# LCD4_3.net
KiCad netlist of a schematic drawn in Altium Designer
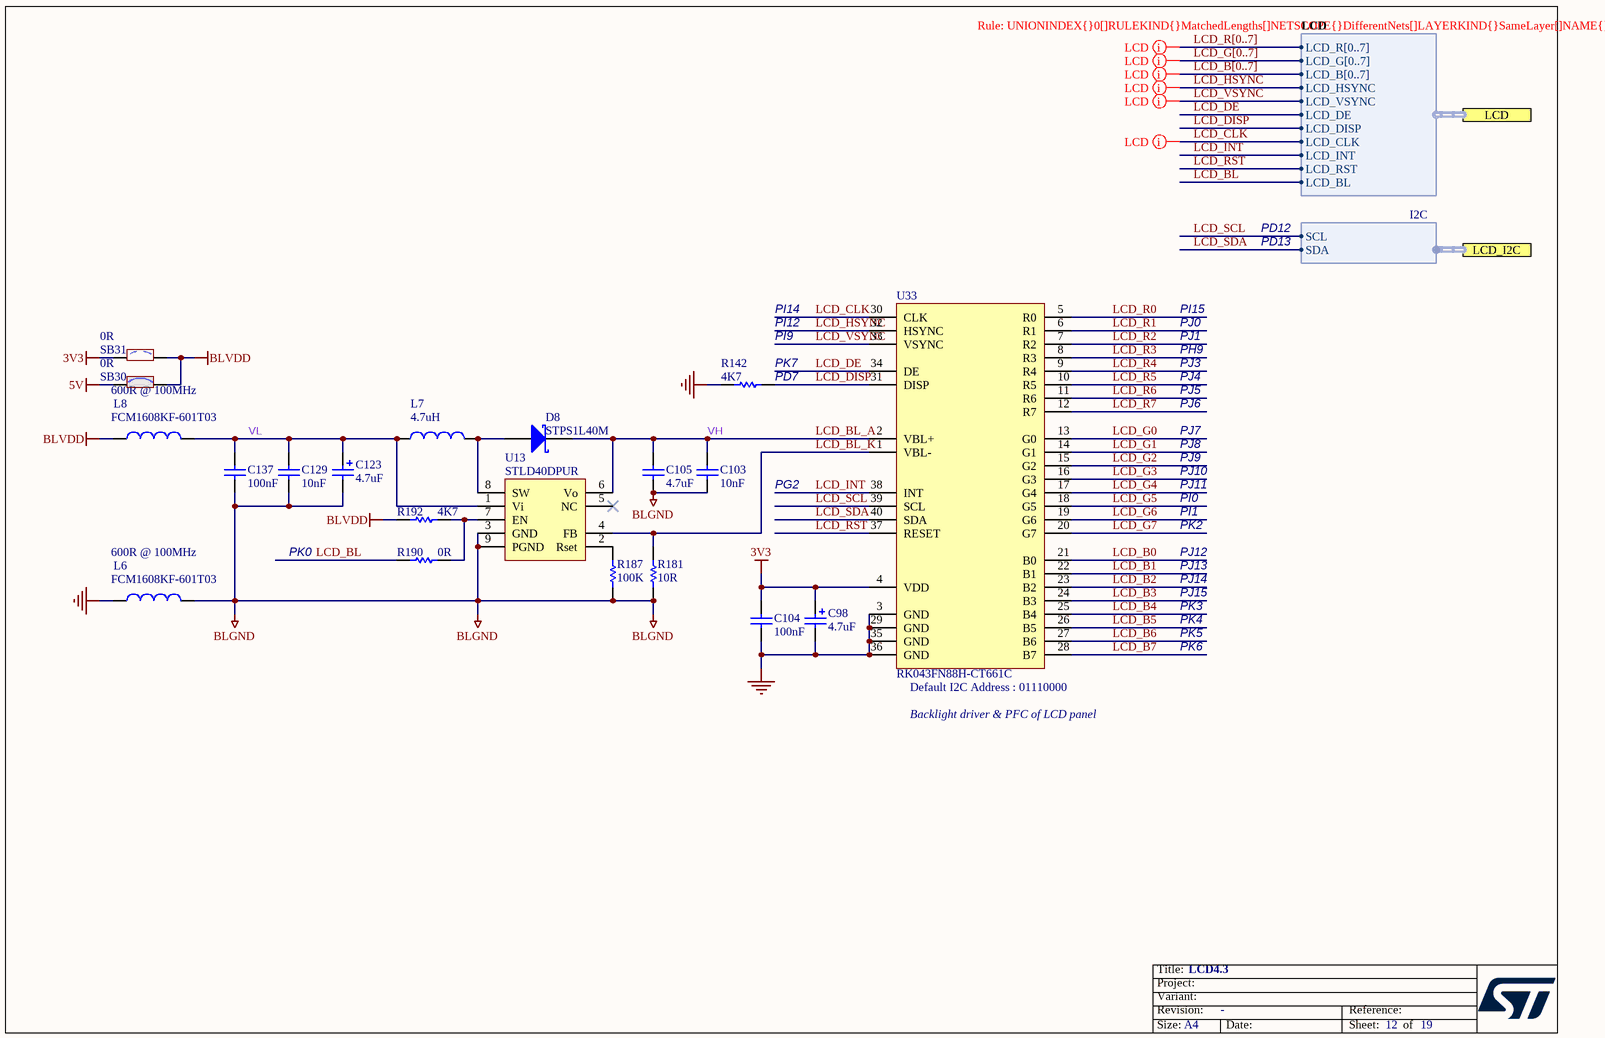
[diagram p0: LCD4.3.SchDoc]

(export (version "E")
  (design (tool "Eeschema 10.0.6"))
  (components
    (comp (ref "C98")
      (value "4.7uF")
      (footprint "CPOL_VISHAY_TANTAL-595D_1407_H220")
      (description "Capacitor, Tantalum, 4.7uF, 16V, +/-10%, 595D case A")
      (fields
        (field (name "INTERNAL_PART_NUMBER") "MCD-00595")
        (field (name "MANUFACTURER_PART_NUMBER") "595D475X9016A2T")
        (field (name "PROVIDED_BY") "Subcon")
      )
      (libsource (lib "MCD_PARTS_database") (part "Cap_POL_TANA"))
    )
    (comp (ref "C103")
      (value "10nF")
      (footprint "C0603")
      (description "Capacitor, MLCC, 10nF, 50V, X7R, +/-10%, 0603, T=0.8mm")
      (fields
        (field (name "INTERNAL_PART_NUMBER") "MCD-00017")
        (field (name "MANUFACTURER_PART_NUMBER") "CC0603KRX7R9BB103")
      )
      (libsource (lib "MCD_PARTS_database") (part "Capacitor"))
    )
    (comp (ref "C104")
      (value "100nF")
      (footprint "C0402")
      (description "Capacitor, MLCC, 100nF, 16V, X7R, +/-10%, 0402, T=0.5mm")
      (fields
        (field (name "INTERNAL_PART_NUMBER") "MCD-00006")
        (field (name "MANUFACTURER_PART_NUMBER") "CC0402KRX7R7BB104")
      )
      (libsource (lib "MCD_PARTS_database") (part "Capacitor"))
    )
    (comp (ref "C105")
      (value "4.7uF")
      (footprint "C1206_H1P25")
      (description "Capacitor, MLCC, 4.7uF, 50V, X7R, 10%, 1206, T=1,27mm")
      (fields
        (field (name "INTERNAL_PART_NUMBER") "MCD-00013")
        (field (name "MANUFACTURER_PART_NUMBER") "12065C475KAT2A")
        (field (name "PROVIDED_BY") "Subcon")
      )
      (libsource (lib "MCD_PARTS_database") (part "Capacitor"))
    )
    (comp (ref "C123")
      (value "4.7uF")
      (footprint "CPOL_VISHAY_TANTAL-595D_1407_H220")
      (description "Capacitor, Tantalum, 4.7uF, 16V, +/-10%, 595D case A")
      (fields
        (field (name "INTERNAL_PART_NUMBER") "MCD-00595")
        (field (name "MANUFACTURER_PART_NUMBER") "595D475X9016A2T")
        (field (name "PROVIDED_BY") "Subcon")
      )
      (libsource (lib "MCD_PARTS_database") (part "Cap_POL_TANA"))
    )
    (comp (ref "C129")
      (value "10nF")
      (footprint "C0603")
      (description "Capacitor, MLCC, 10nF, 50V, X7R, +/-10%, 0603, T=0.8mm")
      (fields
        (field (name "INTERNAL_PART_NUMBER") "MCD-00017")
        (field (name "MANUFACTURER_PART_NUMBER") "CC0603KRX7R9BB103")
      )
      (libsource (lib "MCD_PARTS_database") (part "Capacitor"))
    )
    (comp (ref "C137")
      (value "100nF")
      (footprint "C0402")
      (description "Capacitor, MLCC, 100nF, 16V, X7R, +/-10%, 0402, T=0.5mm")
      (fields
        (field (name "INTERNAL_PART_NUMBER") "MCD-00006")
        (field (name "MANUFACTURER_PART_NUMBER") "CC0402KRX7R7BB104")
      )
      (libsource (lib "MCD_PARTS_database") (part "Capacitor"))
    )
    (comp (ref "D8")
      (value "STPS1L40M")
      (footprint "DIO_DO216-AA")
      (description "Low Drop power Schottky rectifier(1A, 40V, 0.4V)")
      (fields
        (field (name "INTERNAL_PART_NUMBER") "MCD-00033")
        (field (name "MANUFACTURER") "STMICROELECTRONICS")
        (field (name "PROVIDED_BY") "Subcon")
      )
      (libsource (lib "MCD_PARTS_database") (part "STPS1L40M"))
    )
    (comp (ref "L6")
      (value "600R @ 100MHz")
      (footprint "L0603")
      (description "Ferrite bead, 600R @1 00MHz, +/-25%, 350mA, 0R5, 0603, T=0.8mm")
      (fields
        (field (name "INTERNAL_PART_NUMBER") "MCD-00047")
        (field (name "MANUFACTURER_PART_NUMBER") "FCM1608KF-601T03")
        (field (name "MANUFACTURER") "TAI-TECH")
      )
      (libsource (lib "MCD_PARTS_database") (part "BEAD"))
    )
    (comp (ref "L7")
      (value "4.7uH")
      (footprint "L1210_LQH")
      (description "FIXED IND 4.7UH 1A 180 MOHM 30% SMD")
      (fields
        (field (name "INTERNAL_PART_NUMBER") "MCD-00048")
        (field (name "MANUFACTURER_PART_NUMBER") "LQH32PN4R7NN0L")
        (field (name "PROVIDED_BY") "Subcon")
      )
      (libsource (lib "MCD_PARTS_database") (part "Inductor"))
    )
    (comp (ref "L8")
      (value "600R @ 100MHz")
      (footprint "L0603")
      (description "Ferrite bead, 600R @1 00MHz, +/-25%, 350mA, 0R5, 0603, T=0.8mm")
      (fields
        (field (name "INTERNAL_PART_NUMBER") "MCD-00047")
        (field (name "MANUFACTURER_PART_NUMBER") "FCM1608KF-601T03")
        (field (name "MANUFACTURER") "TAI-TECH")
      )
      (libsource (lib "MCD_PARTS_database") (part "BEAD"))
    )
    (comp (ref "R142")
      (value "4K7")
      (footprint "R0603")
      (description "Resistor,4K7,0603,1%,1/10W")
      (fields
        (field (name "INTERNAL_PART_NUMBER") "MCD-00219")
        (field (name "MANUFACTURER_PART_NUMBER") "RC0603FR-074K7L")
        (field (name "PROVIDED_BY") "Subcon")
      )
      (libsource (lib "MCD_PARTS_database") (part "Resistor"))
    )
    (comp (ref "R181")
      (value "10R")
      (footprint "R0805")
      (description "Resistor,10R,0805,1%,Stackpole,1/4W")
      (fields
        (field (name "INTERNAL_PART_NUMBER") "MCD-01111")
        (field (name "MANUFACTURER_PART_NUMBER") "RNCP0805FTD10R0")
        (field (name "PROVIDED_BY") "Subcon")
      )
      (libsource (lib "MCD_PARTS_database") (part "Resistor"))
    )
    (comp (ref "R187")
      (value "100K")
      (footprint "R0402")
      (description "Resistor,100K,0402,1%,1/16W")
      (fields
        (field (name "INTERNAL_PART_NUMBER") "MCD-00059")
        (field (name "MANUFACTURER_PART_NUMBER") "RC0402FR-07100KL")
        (field (name "PROVIDED_BY") "Subcon")
      )
      (libsource (lib "MCD_PARTS_database") (part "Resistor"))
    )
    (comp (ref "R190")
      (value "0R")
      (footprint "R0603")
      (description "Resistor,0R,0603,ULO")
      (fields
        (field (name "INTERNAL_PART_NUMBER") "MCD-00181")
        (field (name "MANUFACTURER_PART_NUMBER") "PMR03EZPJ000")
        (field (name "PROVIDED_BY") "Subcon")
      )
      (libsource (lib "MCD_PARTS_database") (part "Resistor"))
    )
    (comp (ref "R192")
      (value "4K7")
      (footprint "R0603")
      (description "Resistor,4K7,0603,1%,1/10W")
      (fields
        (field (name "INTERNAL_PART_NUMBER") "MCD-00219")
        (field (name "MANUFACTURER_PART_NUMBER") "RC0603FR-074K7L")
        (field (name "PROVIDED_BY") "Subcon")
      )
      (libsource (lib "MCD_PARTS_database") (part "Resistor"))
    )
    (comp (ref "SB30")
      (value "0R")
      (footprint "SOLDER-BRIDGE_R0603-0R")
      (description "Solder Bridge ON")
      (fields
        (field (name "INTERNAL_PART_NUMBER") "MCD-00071")
        (field (name "MANUFACTURER") "YAGEO")
        (field (name "PROVIDED_BY") "Subcon")
      )
      (libsource (lib "MCD_PARTS_database") (part "SB_ON"))
    )
    (comp (ref "SB31")
      (value "0R")
      (footprint "SOLDER-BRIDGE_R0603-0R")
      (description "Solder Bridge OFF")
      (fields (field (name "INTERNAL_PART_NUMBER") "MCD-00072") (field (name "MANUFACTURER") "YAGEO"))
      (libsource (lib "MCD_PARTS_database") (part "SB_OFF"))
    )
    (comp (ref "U13")
      (value "STLD40DPUR")
      (footprint "ICC_QFN8-EPAD_3X3_P065")
      (description "White LED power supply for large display backlight, QFN8")
      (fields
        (field (name "INTERNAL_PART_NUMBER") "MCD-00082")
        (field (name "MANUFACTURER") "STMICROELECTRONICS")
        (field (name "PROVIDED_BY") "Subcon")
      )
      (libsource (lib "MCD_PARTS_database") (part "STLD40DPUR"))
    )
    (comp (ref "U33")
      (value "RK043FN88H-CT661C")
      (footprint "LCD_ROCKTEK_RK043FN48H-CT672B_40P_P080_FLEX-FOLDED")
      (description "LCD, TFT, 4.3-inch, 480(RGB)x272 pixels")
      (fields (field (name "INTERNAL_PART_NUMBER") "MCD-03909") (field (name "MANUFACTURER") "ROCKTECH"))
      (libsource (lib "MCD_PARTS_database") (part "RK043FN78H-CT661C"))
    )
  )
  (nets
    (net (code "3") (name "/LCD_B0") (class "Default")
      (node (ref "U33") (pin "21") (pinfunction "B0_21") (pintype "passive"))
    )
    (net (code "4") (name "/LCD_B1") (class "Default")
      (node (ref "U33") (pin "22") (pinfunction "B1_22") (pintype "passive"))
    )
    (net (code "5") (name "/LCD_B2") (class "Default")
      (node (ref "U33") (pin "23") (pinfunction "B2_23") (pintype "passive"))
    )
    (net (code "6") (name "/LCD_B3") (class "Default")
      (node (ref "U33") (pin "24") (pinfunction "B3_24") (pintype "passive"))
    )
    (net (code "7") (name "/LCD_B4") (class "Default")
      (node (ref "U33") (pin "25") (pinfunction "B4_25") (pintype "passive"))
    )
    (net (code "8") (name "/LCD_B5") (class "Default")
      (node (ref "U33") (pin "26") (pinfunction "B5_26") (pintype "passive"))
    )
    (net (code "9") (name "/LCD_B6") (class "Default")
      (node (ref "U33") (pin "27") (pinfunction "B6_27") (pintype "passive"))
    )
    (net (code "10") (name "/LCD_B7") (class "Default")
      (node (ref "U33") (pin "28") (pinfunction "B7_28") (pintype "passive"))
    )
    (net (code "11") (name "/LCD_BL") (class "Default")
      (node (ref "R190") (pin "1") (pinfunction "1_1") (pintype "passive"))
    )
    (net (code "12") (name "/LCD_BL_A") (class "Default")
      (node (ref "C103") (pin "2") (pinfunction "2_2") (pintype "passive"))
      (node (ref "C105") (pin "2") (pinfunction "2_2") (pintype "passive"))
      (node (ref "D8") (pin "2") (pinfunction "K_2") (pintype "passive"))
      (node (ref "U13") (pin "6") (pinfunction "Vo_6") (pintype "passive"))
      (node (ref "U33") (pin "2") (pinfunction "VBL+_2") (pintype "passive"))
    )
    (net (code "13") (name "/LCD_BL_K") (class "Default")
      (node (ref "R181") (pin "2") (pinfunction "2_2") (pintype "passive"))
      (node (ref "U13") (pin "4") (pinfunction "FB_4") (pintype "passive"))
      (node (ref "U33") (pin "1") (pinfunction "VBL-_1") (pintype "passive"))
    )
    (net (code "15") (name "/LCD_CLK") (class "Default")
      (node (ref "U33") (pin "30") (pinfunction "CLK_30") (pintype "passive"))
    )
    (net (code "16") (name "/LCD_DE") (class "Default")
      (node (ref "U33") (pin "34") (pinfunction "DE_34") (pintype "passive"))
    )
    (net (code "17") (name "/LCD_DISP") (class "Default")
      (node (ref "R142") (pin "2") (pinfunction "2_2") (pintype "passive"))
      (node (ref "U33") (pin "31") (pinfunction "DISP_31") (pintype "passive"))
    )
    (net (code "18") (name "/LCD_G0") (class "Default")
      (node (ref "U33") (pin "13") (pinfunction "G0_13") (pintype "passive"))
    )
    (net (code "19") (name "/LCD_G1") (class "Default")
      (node (ref "U33") (pin "14") (pinfunction "G1_14") (pintype "passive"))
    )
    (net (code "20") (name "/LCD_G2") (class "Default")
      (node (ref "U33") (pin "15") (pinfunction "G2_15") (pintype "passive"))
    )
    (net (code "21") (name "/LCD_G3") (class "Default")
      (node (ref "U33") (pin "16") (pinfunction "G3_16") (pintype "passive"))
    )
    (net (code "22") (name "/LCD_G4") (class "Default")
      (node (ref "U33") (pin "17") (pinfunction "G4_17") (pintype "passive"))
    )
    (net (code "23") (name "/LCD_G5") (class "Default")
      (node (ref "U33") (pin "18") (pinfunction "G5_18") (pintype "passive"))
    )
    (net (code "24") (name "/LCD_G6") (class "Default")
      (node (ref "U33") (pin "19") (pinfunction "G6_19") (pintype "passive"))
    )
    (net (code "25") (name "/LCD_G7") (class "Default")
      (node (ref "U33") (pin "20") (pinfunction "G7_20") (pintype "passive"))
    )
    (net (code "27") (name "/LCD_HSYNC") (class "Default")
      (node (ref "U33") (pin "32") (pinfunction "HSYNC_32") (pintype "passive"))
    )
    (net (code "28") (name "/LCD_INT") (class "Default")
      (node (ref "U33") (pin "38") (pinfunction "INT_38") (pintype "passive"))
    )
    (net (code "29") (name "/LCD_R0") (class "Default")
      (node (ref "U33") (pin "5") (pinfunction "R0_5") (pintype "passive"))
    )
    (net (code "30") (name "/LCD_R1") (class "Default")
      (node (ref "U33") (pin "6") (pinfunction "R1_6") (pintype "passive"))
    )
    (net (code "31") (name "/LCD_R2") (class "Default")
      (node (ref "U33") (pin "7") (pinfunction "R2_7") (pintype "passive"))
    )
    (net (code "32") (name "/LCD_R3") (class "Default")
      (node (ref "U33") (pin "8") (pinfunction "R3_8") (pintype "passive"))
    )
    (net (code "33") (name "/LCD_R4") (class "Default")
      (node (ref "U33") (pin "9") (pinfunction "R4_9") (pintype "passive"))
    )
    (net (code "34") (name "/LCD_R5") (class "Default")
      (node (ref "U33") (pin "10") (pinfunction "R5_10") (pintype "passive"))
    )
    (net (code "35") (name "/LCD_R6") (class "Default")
      (node (ref "U33") (pin "11") (pinfunction "R6_11") (pintype "passive"))
    )
    (net (code "36") (name "/LCD_R7") (class "Default")
      (node (ref "U33") (pin "12") (pinfunction "R7_12") (pintype "passive"))
    )
    (net (code "37") (name "/LCD_RST") (class "Default")
      (node (ref "U33") (pin "37") (pinfunction "RESET_37") (pintype "passive"))
    )
    (net (code "39") (name "/LCD_SCL") (class "Default")
      (node (ref "U33") (pin "39") (pinfunction "SCL_39") (pintype "passive"))
    )
    (net (code "40") (name "/LCD_SDA") (class "Default")
      (node (ref "U33") (pin "40") (pinfunction "SDA_40") (pintype "passive"))
    )
    (net (code "41") (name "/LCD_VSYNC") (class "Default")
      (node (ref "U33") (pin "33") (pinfunction "VSYNC_33") (pintype "passive"))
    )
    (net (code "42") (name "/VL") (class "Default")
      (node (ref "C123") (pin "1") (pinfunction "1_1") (pintype "passive"))
      (node (ref "C129") (pin "2") (pinfunction "2_2") (pintype "passive"))
      (node (ref "C137") (pin "2") (pinfunction "2_2") (pintype "passive"))
      (node (ref "L7") (pin "1") (pinfunction "1_1") (pintype "passive"))
      (node (ref "L8") (pin "2") (pinfunction "2_2") (pintype "passive"))
      (node (ref "U13") (pin "1") (pinfunction "Vi_1") (pintype "passive"))
    )
    (net (code "45") (name "3V3") (class "Default")
      (node (ref "C104") (pin "2") (pinfunction "2_2") (pintype "passive"))
      (node (ref "C98") (pin "1") (pinfunction "1_1") (pintype "passive"))
      (node (ref "SB31") (pin "1") (pinfunction "1_1") (pintype "passive"))
      (node (ref "U33") (pin "4") (pinfunction "VDD_4") (pintype "passive"))
    )
    (net (code "46") (name "5V") (class "Default")
      (node (ref "SB30") (pin "1") (pinfunction "1_1") (pintype "passive"))
    )
    (net (code "47") (name "BLGND") (class "Default")
      (node (ref "C103") (pin "1") (pinfunction "1_1") (pintype "passive"))
      (node (ref "C105") (pin "1") (pinfunction "1_1") (pintype "passive"))
      (node (ref "C123") (pin "2") (pinfunction "2_2") (pintype "passive"))
      (node (ref "C129") (pin "1") (pinfunction "1_1") (pintype "passive"))
      (node (ref "C137") (pin "1") (pinfunction "1_1") (pintype "passive"))
      (node (ref "L6") (pin "2") (pinfunction "2_2") (pintype "passive"))
      (node (ref "R181") (pin "1") (pinfunction "1_1") (pintype "passive"))
      (node (ref "R187") (pin "1") (pinfunction "1_1") (pintype "passive"))
      (node (ref "U13") (pin "3") (pinfunction "GND_3") (pintype "passive"))
      (node (ref "U13") (pin "9") (pinfunction "PGND_9") (pintype "passive"))
    )
    (net (code "48") (name "BLVDD") (class "Default")
      (node (ref "L8") (pin "1") (pinfunction "1_1") (pintype "passive"))
      (node (ref "R192") (pin "1") (pinfunction "1_1") (pintype "passive"))
      (node (ref "SB30") (pin "2") (pinfunction "2_2") (pintype "passive"))
      (node (ref "SB31") (pin "2") (pinfunction "2_2") (pintype "passive"))
    )
    (net (code "49") (name "GND") (class "Default")
      (node (ref "C104") (pin "1") (pinfunction "1_1") (pintype "passive"))
      (node (ref "C98") (pin "2") (pinfunction "2_2") (pintype "passive"))
      (node (ref "L6") (pin "1") (pinfunction "1_1") (pintype "passive"))
      (node (ref "R142") (pin "1") (pinfunction "1_1") (pintype "passive"))
      (node (ref "U33") (pin "29") (pinfunction "GND_29") (pintype "passive"))
      (node (ref "U33") (pin "3") (pinfunction "GND_3") (pintype "passive"))
      (node (ref "U33") (pin "35") (pinfunction "GND_35") (pintype "passive"))
      (node (ref "U33") (pin "36") (pinfunction "GND_36") (pintype "passive"))
    )
    (net (code "50") (name "Net-(D8-A)") (class "Default")
      (node (ref "D8") (pin "1") (pinfunction "A_1") (pintype "passive"))
      (node (ref "L7") (pin "2") (pinfunction "2_2") (pintype "passive"))
      (node (ref "U13") (pin "8") (pinfunction "SW_8") (pintype "passive"))
    )
    (net (code "51") (name "Net-(U13-EN)") (class "Default")
      (node (ref "R190") (pin "2") (pinfunction "2_2") (pintype "passive"))
      (node (ref "R192") (pin "2") (pinfunction "2_2") (pintype "passive"))
      (node (ref "U13") (pin "7") (pinfunction "EN_7") (pintype "passive"))
    )
    (net (code "52") (name "Net-(U13-Rset)") (class "Default")
      (node (ref "R187") (pin "2") (pinfunction "2_2") (pintype "passive"))
      (node (ref "U13") (pin "2") (pinfunction "Rset_2") (pintype "passive"))
    )
    (net (code "53") (name "unconnected-(U13-NC-Pad5)") (class "Default")
      (node (ref "U13") (pin "5") (pinfunction "NC_5") (pintype "passive+no_connect"))
    )
  )
)
